# RaspiOmix.net
KiCad netlist of a schematic drawn in EAGLE
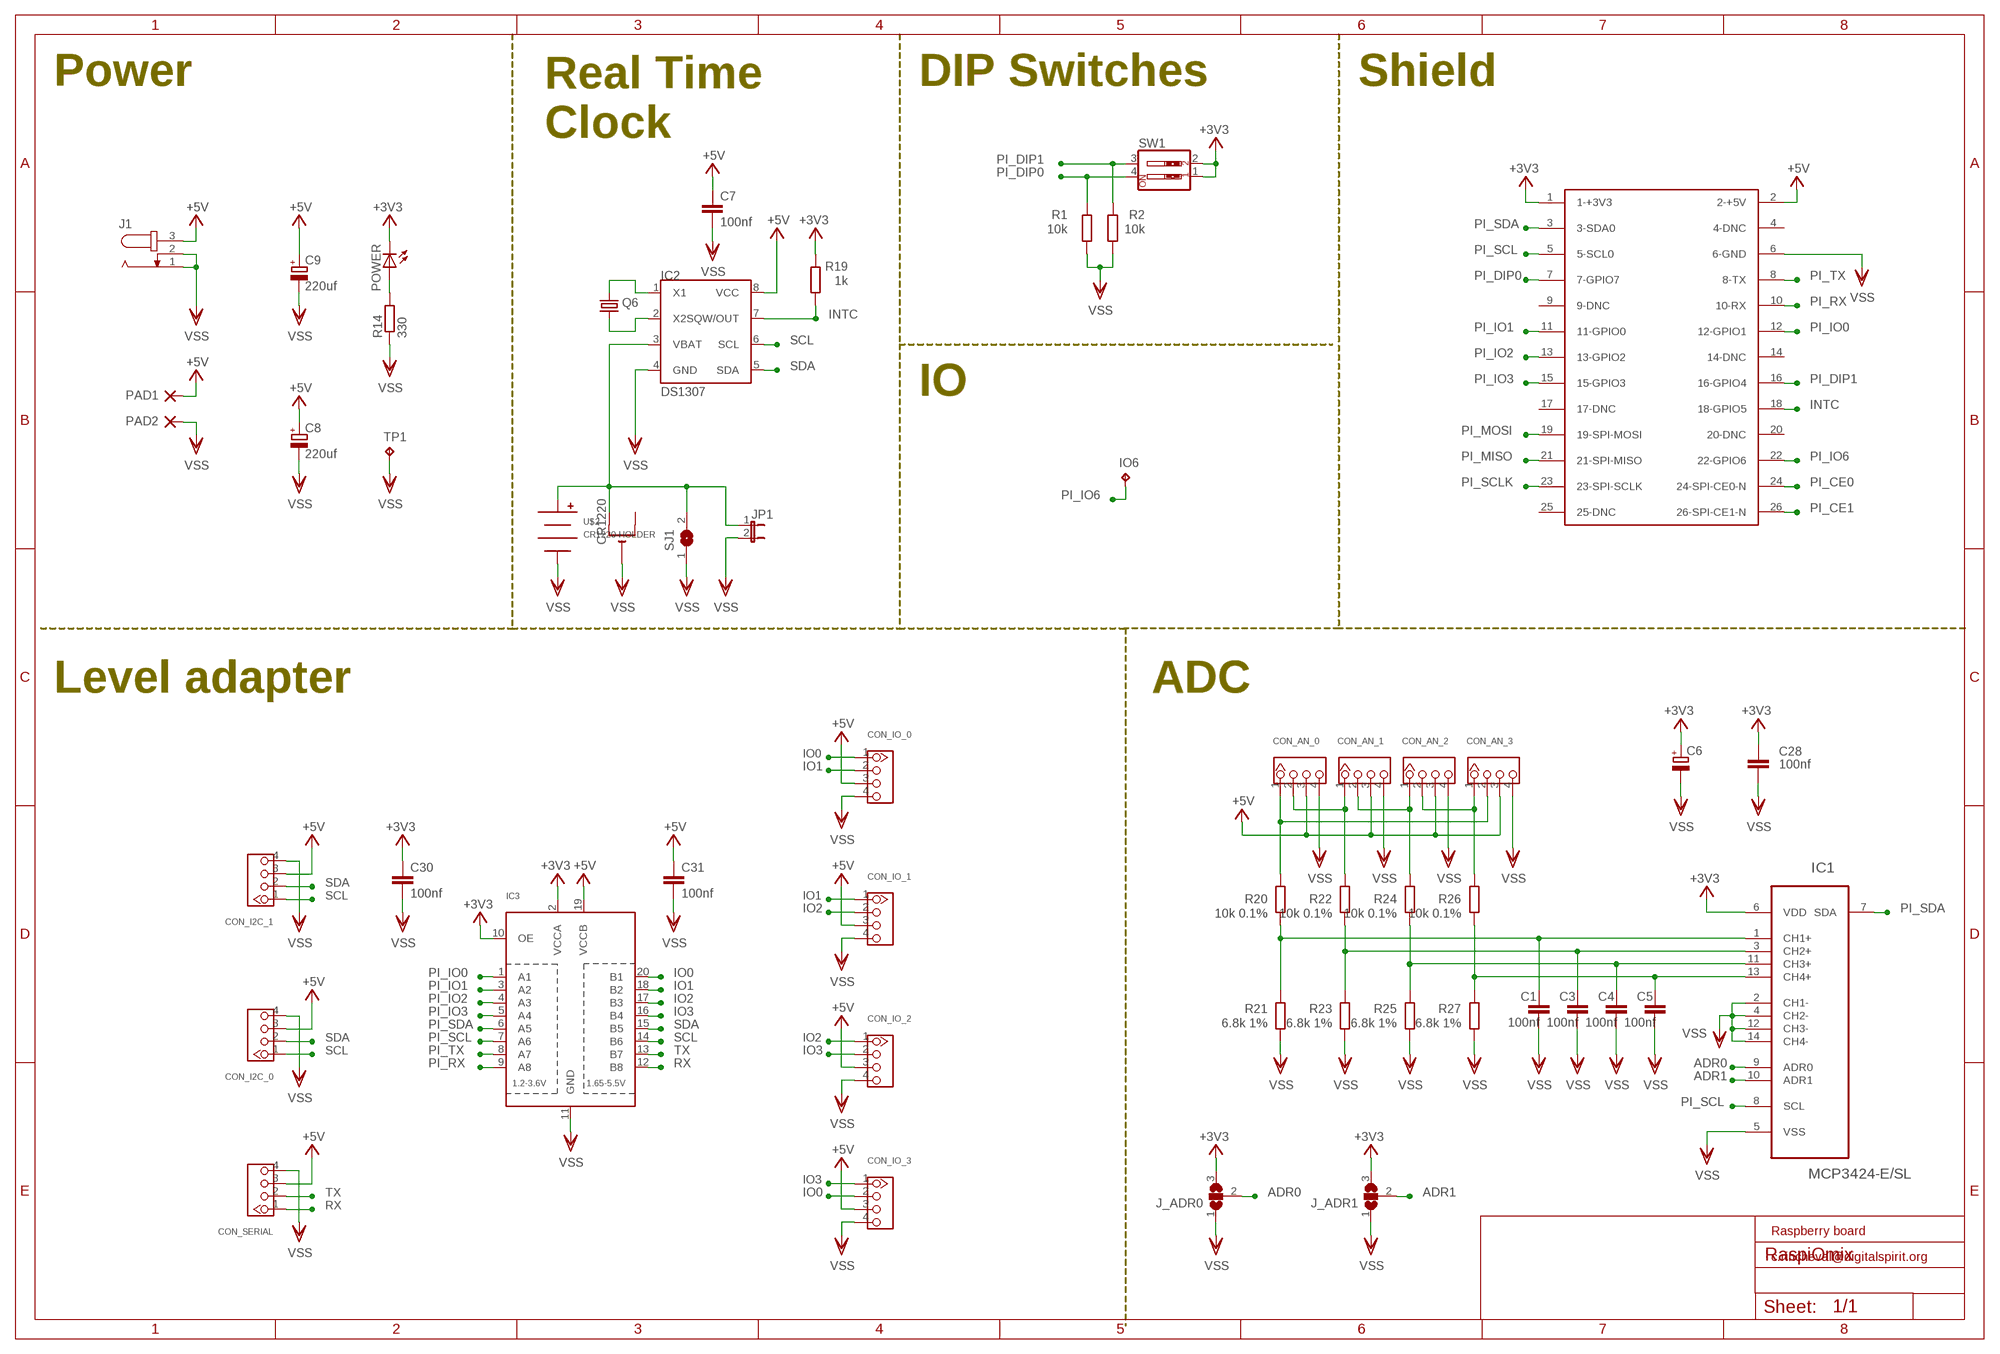
[diagram p0: schematic, sheet 1]

(export (version "E")
  (design (tool "Eeschema 10.0.6"))
  (components
    (comp (ref "C1")
      (value "100nf")
      (footprint "eagle-import:C0805")
      (libsource (lib "eagle-import") (part "C-EUC0805"))
    )
    (comp (ref "C3")
      (value "100nf")
      (footprint "eagle-import:C0805")
      (libsource (lib "eagle-import") (part "C-EUC0805"))
    )
    (comp (ref "C4")
      (value "100nf")
      (footprint "eagle-import:C0805")
      (libsource (lib "eagle-import") (part "C-EUC0805"))
    )
    (comp (ref "C5")
      (value "100nf")
      (footprint "eagle-import:C0805")
      (libsource (lib "eagle-import") (part "C-EUC0805"))
    )
    (comp (ref "C6")
      (value "CPOL-EUB/3528-21R")
      (footprint "eagle-import:B_3528-21R")
      (libsource (lib "eagle-import") (part "CPOL-EUB/3528-21R"))
    )
    (comp (ref "C7")
      (value "100nf")
      (footprint "eagle-import:C0805")
      (libsource (lib "eagle-import") (part "C-EUC0805"))
    )
    (comp (ref "C8")
      (value "220uf")
      (footprint "eagle-import:PANASONIC_D")
      (libsource (lib "eagle-import") (part "CPOL-EUD"))
    )
    (comp (ref "C9")
      (value "220uf")
      (footprint "eagle-import:PANASONIC_D")
      (libsource (lib "eagle-import") (part "CPOL-EUD"))
    )
    (comp (ref "C28")
      (value "100nf")
      (footprint "eagle-import:C0805")
      (libsource (lib "eagle-import") (part "C-EUC0805"))
    )
    (comp (ref "C30")
      (value "100nf")
      (footprint "eagle-import:C0805")
      (libsource (lib "eagle-import") (part "C-EUC0805"))
    )
    (comp (ref "C31")
      (value "100nf")
      (footprint "eagle-import:C0805")
      (libsource (lib "eagle-import") (part "C-EUC0805"))
    )
    (comp (ref "CON_AN_0")
      (value "TWIG-4P-2.0'90D'")
      (footprint "eagle-import:4P-2.0-90D")
      (libsource (lib "eagle-import") (part "TWIG-4P-2.0'90D'"))
    )
    (comp (ref "CON_AN_1")
      (value "TWIG-4P-2.0'90D'")
      (footprint "eagle-import:4P-2.0-90D")
      (libsource (lib "eagle-import") (part "TWIG-4P-2.0'90D'"))
    )
    (comp (ref "CON_AN_2")
      (value "TWIG-4P-2.0'90D'")
      (footprint "eagle-import:4P-2.0-90D")
      (libsource (lib "eagle-import") (part "TWIG-4P-2.0'90D'"))
    )
    (comp (ref "CON_AN_3")
      (value "TWIG-4P-2.0'90D'")
      (footprint "eagle-import:4P-2.0-90D")
      (libsource (lib "eagle-import") (part "TWIG-4P-2.0'90D'"))
    )
    (comp (ref "CON_I2C_0")
      (value "TWIG-4P-2.0'90D'")
      (footprint "eagle-import:4P-2.0-90D")
      (libsource (lib "eagle-import") (part "TWIG-4P-2.0'90D'"))
    )
    (comp (ref "CON_I2C_1")
      (value "TWIG-4P-2.0'90D'")
      (footprint "eagle-import:4P-2.0-90D")
      (libsource (lib "eagle-import") (part "TWIG-4P-2.0'90D'"))
    )
    (comp (ref "CON_IO_0")
      (value "TWIG-4P-2.0'90D'")
      (footprint "eagle-import:4P-2.0-90D")
      (libsource (lib "eagle-import") (part "TWIG-4P-2.0'90D'"))
    )
    (comp (ref "CON_IO_1")
      (value "TWIG-4P-2.0'90D'")
      (footprint "eagle-import:4P-2.0-90D")
      (libsource (lib "eagle-import") (part "TWIG-4P-2.0'90D'"))
    )
    (comp (ref "CON_IO_2")
      (value "TWIG-4P-2.0'90D'")
      (footprint "eagle-import:4P-2.0-90D")
      (libsource (lib "eagle-import") (part "TWIG-4P-2.0'90D'"))
    )
    (comp (ref "CON_IO_3")
      (value "TWIG-4P-2.0'90D'")
      (footprint "eagle-import:4P-2.0-90D")
      (libsource (lib "eagle-import") (part "TWIG-4P-2.0'90D'"))
    )
    (comp (ref "CON_SERIAL")
      (value "TWIG-4P-2.0'90D'")
      (footprint "eagle-import:4P-2.0-90D")
      (libsource (lib "eagle-import") (part "TWIG-4P-2.0'90D'"))
    )
    (comp (ref "CR1220")
      (value "CR1220THM")
      (footprint "eagle-import:CR1220-THM")
      (libsource (lib "eagle-import") (part "CR1220THM"))
    )
    (comp (ref "IC1")
      (value "MCP3424-E/SL")
      (footprint "eagle-import:SOIC-14")
      (libsource (lib "eagle-import") (part "MCP3424-E/SL"))
    )
    (comp (ref "IC2")
      (value "DS1307")
      (footprint "eagle-import:SOIC-8")
      (libsource (lib "eagle-import") (part "DS1307"))
    )
    (comp (ref "IC3")
      (value "TXB0108PWR")
      (footprint "eagle-import:TSSOP20")
      (libsource (lib "eagle-import") (part "TXB0108PWR"))
    )
    (comp (ref "IO6")
      (value "TPPAD1-13")
      (footprint "eagle-import:P1-13")
      (libsource (lib "eagle-import") (part "TPPAD1-13"))
    )
    (comp (ref "J1")
      (value "JACK-PLUG0")
      (footprint "eagle-import:SPC4077")
      (libsource (lib "eagle-import") (part "JACK-PLUG0"))
    )
    (comp (ref "JP1")
      (value "JP1E")
      (footprint "eagle-import:JP1")
      (libsource (lib "eagle-import") (part "JP1E"))
    )
    (comp (ref "J_ADR0")
      (value "SJ2W")
      (footprint "eagle-import:SJ_2")
      (libsource (lib "eagle-import") (part "SJ2W"))
    )
    (comp (ref "J_ADR1")
      (value "SJ2W")
      (footprint "eagle-import:SJ_2")
      (libsource (lib "eagle-import") (part "SJ2W"))
    )
    (comp (ref "PAD1")
      (value "WIREPAD3,17/1,3")
      (footprint "eagle-import:3,17_1,3")
      (libsource (lib "eagle-import") (part "WIREPAD3,17/1,3"))
    )
    (comp (ref "PAD2")
      (value "WIREPAD3,17/1,3")
      (footprint "eagle-import:3,17_1,3")
      (libsource (lib "eagle-import") (part "WIREPAD3,17/1,3"))
    )
    (comp (ref "POWER")
      (value "LEDCHIPLED_0805")
      (footprint "eagle-import:CHIPLED_0805")
      (libsource (lib "eagle-import") (part "LEDCHIPLED_0805"))
    )
    (comp (ref "Q6")
      (value "CRYSTALTC26H")
      (footprint "eagle-import:TC26H")
      (libsource (lib "eagle-import") (part "CRYSTALTC26H"))
    )
    (comp (ref "R1")
      (value "10k")
      (footprint "eagle-import:M0805")
      (libsource (lib "eagle-import") (part "R-EU_M0805"))
    )
    (comp (ref "R2")
      (value "10k")
      (footprint "eagle-import:M0805")
      (libsource (lib "eagle-import") (part "R-EU_M0805"))
    )
    (comp (ref "R14")
      (value "330")
      (footprint "eagle-import:M0805")
      (libsource (lib "eagle-import") (part "R-EU_M0805"))
    )
    (comp (ref "R19")
      (value "1k")
      (footprint "eagle-import:M0805")
      (libsource (lib "eagle-import") (part "R-EU_M0805"))
    )
    (comp (ref "R20")
      (value "10k 0.1%")
      (footprint "eagle-import:M0805")
      (libsource (lib "eagle-import") (part "R-EU_M0805"))
    )
    (comp (ref "R21")
      (value "6.8k 1%")
      (footprint "eagle-import:M0805")
      (libsource (lib "eagle-import") (part "R-EU_M0805"))
    )
    (comp (ref "R22")
      (value "10k 0.1%")
      (footprint "eagle-import:M0805")
      (libsource (lib "eagle-import") (part "R-EU_M0805"))
    )
    (comp (ref "R23")
      (value "6.8k 1%")
      (footprint "eagle-import:M0805")
      (libsource (lib "eagle-import") (part "R-EU_M0805"))
    )
    (comp (ref "R24")
      (value "10k 0.1%")
      (footprint "eagle-import:M0805")
      (libsource (lib "eagle-import") (part "R-EU_M0805"))
    )
    (comp (ref "R25")
      (value "6.8k 1%")
      (footprint "eagle-import:M0805")
      (libsource (lib "eagle-import") (part "R-EU_M0805"))
    )
    (comp (ref "R26")
      (value "10k 0.1%")
      (footprint "eagle-import:M0805")
      (libsource (lib "eagle-import") (part "R-EU_M0805"))
    )
    (comp (ref "R27")
      (value "6.8k 1%")
      (footprint "eagle-import:M0805")
      (libsource (lib "eagle-import") (part "R-EU_M0805"))
    )
    (comp (ref "SJ1") (value "SJ") (footprint "eagle-import:SJ") (libsource (lib "eagle-import") (part "SJ")))
    (comp (ref "SW1")
      (value "SW_DIP-2")
      (footprint "eagle-import:EDG-02")
      (libsource (lib "eagle-import") (part "SW_DIP-2"))
    )
    (comp (ref "TP1")
      (value "TPPAD1-13")
      (footprint "eagle-import:P1-13")
      (libsource (lib "eagle-import") (part "TPPAD1-13"))
    )
    (comp (ref "U$2")
      (value "CR1220-HOLDER")
      (footprint "eagle-import:HARWIN-CR1220")
      (libsource (lib "eagle-import") (part "CR1220-HOLDER"))
    )
    (comp (ref "U$3")
      (value "RASPBERRY-PILIGHT-HOLE")
      (footprint "eagle-import:RASPBERRY-PI-LIGHT-HOLE")
      (libsource (lib "eagle-import") (part "RASPBERRY-PILIGHT-HOLE"))
    )
  )
  (nets
    (net (code "1") (name "+3V3") (class "Default")
      (node (ref "C28") (pin "2") (pinfunction "2_2") (pintype "passive"))
      (node (ref "C30") (pin "1") (pinfunction "1_1") (pintype "passive"))
      (node (ref "C6") (pin "+") (pinfunction "+_+") (pintype "passive"))
      (node (ref "IC1") (pin "6") (pinfunction "VDD_6") (pintype "power_in"))
      (node (ref "IC3") (pin "10") (pinfunction "OE_10") (pintype "bidirectional"))
      (node (ref "IC3") (pin "2") (pinfunction "VCCA_2") (pintype "bidirectional"))
      (node (ref "J_ADR0") (pin "3") (pinfunction "3_3") (pintype "passive"))
      (node (ref "J_ADR1") (pin "3") (pinfunction "3_3") (pintype "passive"))
      (node (ref "POWER") (pin "C") (pinfunction "C_C") (pintype "passive"))
      (node (ref "R19") (pin "2") (pinfunction "2_2") (pintype "passive"))
      (node (ref "SW1") (pin "1") (pinfunction "1_1") (pintype "passive"))
      (node (ref "SW1") (pin "2") (pinfunction "2_2") (pintype "passive"))
      (node (ref "U$3") (pin "1") (pinfunction "1-+3V3_1") (pintype "bidirectional"))
    )
    (net (code "2") (name "+5V") (class "Default")
      (node (ref "C31") (pin "1") (pinfunction "1_1") (pintype "passive"))
      (node (ref "C7") (pin "1") (pinfunction "1_1") (pintype "passive"))
      (node (ref "C8") (pin "+") (pinfunction "+_+") (pintype "passive"))
      (node (ref "C9") (pin "+") (pinfunction "+_+") (pintype "passive"))
      (node (ref "CON_AN_0") (pin "3") (pinfunction "3_3") (pintype "bidirectional"))
      (node (ref "CON_AN_1") (pin "3") (pinfunction "3_3") (pintype "bidirectional"))
      (node (ref "CON_AN_2") (pin "3") (pinfunction "3_3") (pintype "bidirectional"))
      (node (ref "CON_AN_3") (pin "3") (pinfunction "3_3") (pintype "bidirectional"))
      (node (ref "CON_I2C_0") (pin "3") (pinfunction "3_3") (pintype "bidirectional"))
      (node (ref "CON_I2C_1") (pin "3") (pinfunction "3_3") (pintype "bidirectional"))
      (node (ref "CON_IO_0") (pin "3") (pinfunction "3_3") (pintype "bidirectional"))
      (node (ref "CON_IO_1") (pin "3") (pinfunction "3_3") (pintype "bidirectional"))
      (node (ref "CON_IO_2") (pin "3") (pinfunction "3_3") (pintype "bidirectional"))
      (node (ref "CON_IO_3") (pin "3") (pinfunction "3_3") (pintype "bidirectional"))
      (node (ref "CON_SERIAL") (pin "3") (pinfunction "3_3") (pintype "bidirectional"))
      (node (ref "IC2") (pin "8") (pinfunction "VCC_8") (pintype "power_in"))
      (node (ref "IC3") (pin "19") (pinfunction "VCCB_19") (pintype "bidirectional"))
      (node (ref "J1") (pin "3") (pinfunction "3_3") (pintype "passive"))
      (node (ref "PAD1") (pin "1") (pinfunction "P_1") (pintype "passive"))
      (node (ref "U$3") (pin "2") (pinfunction "2-+5V_2") (pintype "bidirectional"))
    )
    (net (code "3") (name "/ADR0") (class "Default")
      (node (ref "IC1") (pin "9") (pinfunction "ADR0_9") (pintype "input"))
      (node (ref "J_ADR0") (pin "2") (pinfunction "2_2") (pintype "passive"))
    )
    (net (code "4") (name "/ADR1") (class "Default")
      (node (ref "IC1") (pin "10") (pinfunction "ADR1_10") (pintype "input"))
      (node (ref "J_ADR1") (pin "2") (pinfunction "2_2") (pintype "passive"))
    )
    (net (code "5") (name "/INTC") (class "Default")
      (node (ref "IC2") (pin "7") (pinfunction "SQW/OUT_7") (pintype "output"))
      (node (ref "R19") (pin "1") (pinfunction "1_1") (pintype "passive"))
      (node (ref "U$3") (pin "18") (pinfunction "18-GPIO5_18") (pintype "bidirectional"))
    )
    (net (code "6") (name "/IO0") (class "Default")
      (node (ref "CON_IO_0") (pin "1") (pinfunction "1_1") (pintype "bidirectional"))
      (node (ref "CON_IO_3") (pin "2") (pinfunction "2_2") (pintype "bidirectional"))
      (node (ref "IC3") (pin "20") (pinfunction "B1_20") (pintype "bidirectional"))
    )
    (net (code "7") (name "/IO1") (class "Default")
      (node (ref "CON_IO_0") (pin "2") (pinfunction "2_2") (pintype "bidirectional"))
      (node (ref "CON_IO_1") (pin "1") (pinfunction "1_1") (pintype "bidirectional"))
      (node (ref "IC3") (pin "18") (pinfunction "B2_18") (pintype "bidirectional"))
    )
    (net (code "8") (name "/IO2") (class "Default")
      (node (ref "CON_IO_1") (pin "2") (pinfunction "2_2") (pintype "bidirectional"))
      (node (ref "CON_IO_2") (pin "1") (pinfunction "1_1") (pintype "bidirectional"))
      (node (ref "IC3") (pin "17") (pinfunction "B3_17") (pintype "bidirectional"))
    )
    (net (code "9") (name "/IO3") (class "Default")
      (node (ref "CON_IO_2") (pin "2") (pinfunction "2_2") (pintype "bidirectional"))
      (node (ref "CON_IO_3") (pin "1") (pinfunction "1_1") (pintype "bidirectional"))
      (node (ref "IC3") (pin "16") (pinfunction "B4_16") (pintype "bidirectional"))
    )
    (net (code "10") (name "/PI_CE0") (class "Default")
      (node (ref "U$3") (pin "24") (pinfunction "24-SPI-CE0-N_24") (pintype "bidirectional"))
    )
    (net (code "11") (name "/PI_CE1") (class "Default")
      (node (ref "U$3") (pin "26") (pinfunction "26-SPI-CE1-N_26") (pintype "bidirectional"))
    )
    (net (code "12") (name "/PI_DIP0") (class "Default")
      (node (ref "R1") (pin "2") (pinfunction "2_2") (pintype "passive"))
      (node (ref "SW1") (pin "4") (pinfunction "4_4") (pintype "passive"))
      (node (ref "U$3") (pin "7") (pinfunction "7-GPIO7_7") (pintype "bidirectional"))
    )
    (net (code "13") (name "/PI_DIP1") (class "Default")
      (node (ref "R2") (pin "2") (pinfunction "2_2") (pintype "passive"))
      (node (ref "SW1") (pin "3") (pinfunction "3_3") (pintype "passive"))
      (node (ref "U$3") (pin "16") (pinfunction "16-GPIO4_16") (pintype "bidirectional"))
    )
    (net (code "14") (name "/PI_IO0") (class "Default")
      (node (ref "IC3") (pin "1") (pinfunction "A1_1") (pintype "bidirectional"))
      (node (ref "U$3") (pin "12") (pinfunction "12-GPIO1_12") (pintype "bidirectional"))
    )
    (net (code "15") (name "/PI_IO1") (class "Default")
      (node (ref "IC3") (pin "3") (pinfunction "A2_3") (pintype "bidirectional"))
      (node (ref "U$3") (pin "11") (pinfunction "11-GPIO0_11") (pintype "bidirectional"))
    )
    (net (code "16") (name "/PI_IO2") (class "Default")
      (node (ref "IC3") (pin "4") (pinfunction "A3_4") (pintype "bidirectional"))
      (node (ref "U$3") (pin "13") (pinfunction "13-GPIO2_13") (pintype "bidirectional"))
    )
    (net (code "17") (name "/PI_IO3") (class "Default")
      (node (ref "IC3") (pin "5") (pinfunction "A4_5") (pintype "bidirectional"))
      (node (ref "U$3") (pin "15") (pinfunction "15-GPIO3_15") (pintype "bidirectional"))
    )
    (net (code "18") (name "/PI_IO6") (class "Default")
      (node (ref "IO6") (pin "TP") (pinfunction "TP_TP") (pintype "input"))
      (node (ref "U$3") (pin "22") (pinfunction "22-GPIO6_22") (pintype "bidirectional"))
    )
    (net (code "19") (name "/PI_MISO") (class "Default")
      (node (ref "U$3") (pin "21") (pinfunction "21-SPI-MISO_21") (pintype "bidirectional"))
    )
    (net (code "20") (name "/PI_MOSI") (class "Default")
      (node (ref "U$3") (pin "19") (pinfunction "19-SPI-MOSI_19") (pintype "bidirectional"))
    )
    (net (code "21") (name "/PI_RX") (class "Default")
      (node (ref "IC3") (pin "9") (pinfunction "A8_9") (pintype "bidirectional"))
      (node (ref "U$3") (pin "10") (pinfunction "10-RX_10") (pintype "bidirectional"))
    )
    (net (code "22") (name "/PI_SCL") (class "Default")
      (node (ref "IC1") (pin "8") (pinfunction "SCL_8") (pintype "input"))
      (node (ref "IC3") (pin "7") (pinfunction "A6_7") (pintype "bidirectional"))
      (node (ref "U$3") (pin "5") (pinfunction "5-SCL0_5") (pintype "bidirectional"))
    )
    (net (code "23") (name "/PI_SCLK") (class "Default")
      (node (ref "U$3") (pin "23") (pinfunction "23-SPI-SCLK_23") (pintype "bidirectional"))
    )
    (net (code "24") (name "/PI_SDA") (class "Default")
      (node (ref "IC1") (pin "7") (pinfunction "SDA_7") (pintype "bidirectional"))
      (node (ref "IC3") (pin "6") (pinfunction "A5_6") (pintype "bidirectional"))
      (node (ref "U$3") (pin "3") (pinfunction "3-SDA0_3") (pintype "bidirectional"))
    )
    (net (code "25") (name "/PI_TX") (class "Default")
      (node (ref "IC3") (pin "8") (pinfunction "A7_8") (pintype "bidirectional"))
      (node (ref "U$3") (pin "8") (pinfunction "8-TX_8") (pintype "bidirectional"))
    )
    (net (code "26") (name "/RX") (class "Default")
      (node (ref "CON_SERIAL") (pin "1") (pinfunction "1_1") (pintype "bidirectional"))
      (node (ref "IC3") (pin "12") (pinfunction "B8_12") (pintype "bidirectional"))
    )
    (net (code "27") (name "/SCL") (class "Default")
      (node (ref "CON_I2C_0") (pin "1") (pinfunction "1_1") (pintype "bidirectional"))
      (node (ref "CON_I2C_1") (pin "1") (pinfunction "1_1") (pintype "bidirectional"))
      (node (ref "IC2") (pin "6") (pinfunction "SCL_6") (pintype "input"))
      (node (ref "IC3") (pin "14") (pinfunction "B6_14") (pintype "bidirectional"))
    )
    (net (code "28") (name "/SDA") (class "Default")
      (node (ref "CON_I2C_0") (pin "2") (pinfunction "2_2") (pintype "bidirectional"))
      (node (ref "CON_I2C_1") (pin "2") (pinfunction "2_2") (pintype "bidirectional"))
      (node (ref "IC2") (pin "5") (pinfunction "SDA_5") (pintype "bidirectional"))
      (node (ref "IC3") (pin "15") (pinfunction "B5_15") (pintype "bidirectional"))
    )
    (net (code "29") (name "/TX") (class "Default")
      (node (ref "CON_SERIAL") (pin "2") (pinfunction "2_2") (pintype "bidirectional"))
      (node (ref "IC3") (pin "13") (pinfunction "B7_13") (pintype "bidirectional"))
    )
    (net (code "30") (name "Net-(CON_AN_0-Pad1)") (class "Default")
      (node (ref "CON_AN_0") (pin "1") (pinfunction "1_1") (pintype "bidirectional"))
      (node (ref "CON_AN_3") (pin "2") (pinfunction "2_2") (pintype "bidirectional"))
      (node (ref "R20") (pin "2") (pinfunction "2_2") (pintype "passive"))
    )
    (net (code "31") (name "Net-(CON_AN_0-Pad2)") (class "Default")
      (node (ref "CON_AN_0") (pin "2") (pinfunction "2_2") (pintype "bidirectional"))
      (node (ref "CON_AN_1") (pin "1") (pinfunction "1_1") (pintype "bidirectional"))
      (node (ref "R22") (pin "2") (pinfunction "2_2") (pintype "passive"))
    )
    (net (code "32") (name "Net-(CON_AN_1-Pad2)") (class "Default")
      (node (ref "CON_AN_1") (pin "2") (pinfunction "2_2") (pintype "bidirectional"))
      (node (ref "CON_AN_2") (pin "1") (pinfunction "1_1") (pintype "bidirectional"))
      (node (ref "R24") (pin "2") (pinfunction "2_2") (pintype "passive"))
    )
    (net (code "33") (name "Net-(CON_AN_2-Pad2)") (class "Default")
      (node (ref "CON_AN_2") (pin "2") (pinfunction "2_2") (pintype "bidirectional"))
      (node (ref "CON_AN_3") (pin "1") (pinfunction "1_1") (pintype "bidirectional"))
      (node (ref "R26") (pin "2") (pinfunction "2_2") (pintype "passive"))
    )
    (net (code "34") (name "Net-(CR1220-+)") (class "Default")
      (node (ref "CR1220") (pin "+1") (pinfunction "+_+1") (pintype "passive"))
      (node (ref "IC2") (pin "3") (pinfunction "VBAT_3") (pintype "power_in"))
      (node (ref "JP1") (pin "1") (pinfunction "1_1") (pintype "passive"))
      (node (ref "SJ1") (pin "2") (pinfunction "2_2") (pintype "passive"))
      (node (ref "U$2") (pin "POS") (pinfunction "POS_POS") (pintype "bidirectional"))
    )
    (net (code "35") (name "Net-(IC1-CH1+)") (class "Default")
      (node (ref "C1") (pin "1") (pinfunction "1_1") (pintype "passive"))
      (node (ref "IC1") (pin "1") (pinfunction "CH1+_1") (pintype "input"))
      (node (ref "R20") (pin "1") (pinfunction "1_1") (pintype "passive"))
      (node (ref "R21") (pin "2") (pinfunction "2_2") (pintype "passive"))
    )
    (net (code "36") (name "Net-(IC1-CH2+)") (class "Default")
      (node (ref "C3") (pin "1") (pinfunction "1_1") (pintype "passive"))
      (node (ref "IC1") (pin "3") (pinfunction "CH2+_3") (pintype "input"))
      (node (ref "R22") (pin "1") (pinfunction "1_1") (pintype "passive"))
      (node (ref "R23") (pin "2") (pinfunction "2_2") (pintype "passive"))
    )
    (net (code "37") (name "Net-(IC1-CH3+)") (class "Default")
      (node (ref "C4") (pin "1") (pinfunction "1_1") (pintype "passive"))
      (node (ref "IC1") (pin "11") (pinfunction "CH3+_11") (pintype "input"))
      (node (ref "R24") (pin "1") (pinfunction "1_1") (pintype "passive"))
      (node (ref "R25") (pin "2") (pinfunction "2_2") (pintype "passive"))
    )
    (net (code "38") (name "Net-(IC1-CH4+)") (class "Default")
      (node (ref "C5") (pin "1") (pinfunction "1_1") (pintype "passive"))
      (node (ref "IC1") (pin "13") (pinfunction "CH4+_13") (pintype "input"))
      (node (ref "R26") (pin "1") (pinfunction "1_1") (pintype "passive"))
      (node (ref "R27") (pin "2") (pinfunction "2_2") (pintype "passive"))
    )
    (net (code "39") (name "Net-(IC2-X1)") (class "Default")
      (node (ref "IC2") (pin "1") (pinfunction "X1_1") (pintype "input"))
      (node (ref "Q6") (pin "1") (pinfunction "1_1") (pintype "passive"))
    )
    (net (code "40") (name "Net-(IC2-X2)") (class "Default")
      (node (ref "IC2") (pin "2") (pinfunction "X2_2") (pintype "output"))
      (node (ref "Q6") (pin "2") (pinfunction "2_2") (pintype "passive"))
    )
    (net (code "41") (name "Net-(POWER-PadA)") (class "Default")
      (node (ref "POWER") (pin "A") (pinfunction "A_A") (pintype "passive"))
      (node (ref "R14") (pin "2") (pinfunction "2_2") (pintype "passive"))
    )
    (net (code "42") (name "VSS") (class "Default")
      (node (ref "C1") (pin "2") (pinfunction "2_2") (pintype "passive"))
      (node (ref "C28") (pin "1") (pinfunction "1_1") (pintype "passive"))
      (node (ref "C3") (pin "2") (pinfunction "2_2") (pintype "passive"))
      (node (ref "C30") (pin "2") (pinfunction "2_2") (pintype "passive"))
      (node (ref "C31") (pin "2") (pinfunction "2_2") (pintype "passive"))
      (node (ref "C4") (pin "2") (pinfunction "2_2") (pintype "passive"))
      (node (ref "C5") (pin "2") (pinfunction "2_2") (pintype "passive"))
      (node (ref "C6") (pin "-") (pinfunction "-_-") (pintype "passive"))
      (node (ref "C7") (pin "2") (pinfunction "2_2") (pintype "passive"))
      (node (ref "C8") (pin "-") (pinfunction "-_-") (pintype "passive"))
      (node (ref "C9") (pin "-") (pinfunction "-_-") (pintype "passive"))
      (node (ref "CON_AN_0") (pin "4") (pinfunction "4_4") (pintype "bidirectional"))
      (node (ref "CON_AN_1") (pin "4") (pinfunction "4_4") (pintype "bidirectional"))
      (node (ref "CON_AN_2") (pin "4") (pinfunction "4_4") (pintype "bidirectional"))
      (node (ref "CON_AN_3") (pin "4") (pinfunction "4_4") (pintype "bidirectional"))
      (node (ref "CON_I2C_0") (pin "4") (pinfunction "4_4") (pintype "bidirectional"))
      (node (ref "CON_I2C_1") (pin "4") (pinfunction "4_4") (pintype "bidirectional"))
      (node (ref "CON_IO_0") (pin "4") (pinfunction "4_4") (pintype "bidirectional"))
      (node (ref "CON_IO_1") (pin "4") (pinfunction "4_4") (pintype "bidirectional"))
      (node (ref "CON_IO_2") (pin "4") (pinfunction "4_4") (pintype "bidirectional"))
      (node (ref "CON_IO_3") (pin "4") (pinfunction "4_4") (pintype "bidirectional"))
      (node (ref "CON_SERIAL") (pin "4") (pinfunction "4_4") (pintype "bidirectional"))
      (node (ref "CR1220") (pin "-") (pinfunction "-_-") (pintype "passive"))
      (node (ref "IC1") (pin "12") (pinfunction "CH3-_12") (pintype "input"))
      (node (ref "IC1") (pin "14") (pinfunction "CH4-_14") (pintype "input"))
      (node (ref "IC1") (pin "2") (pinfunction "CH1-_2") (pintype "input"))
      (node (ref "IC1") (pin "4") (pinfunction "CH2-_4") (pintype "input"))
      (node (ref "IC1") (pin "5") (pinfunction "VSS_5") (pintype "power_in"))
      (node (ref "IC2") (pin "4") (pinfunction "GND_4") (pintype "power_in"))
      (node (ref "IC3") (pin "11") (pinfunction "GND_11") (pintype "bidirectional"))
      (node (ref "J1") (pin "1") (pinfunction "1_1") (pintype "passive"))
      (node (ref "J1") (pin "2") (pinfunction "2_2") (pintype "passive"))
      (node (ref "JP1") (pin "2") (pinfunction "2_2") (pintype "passive"))
      (node (ref "J_ADR0") (pin "1") (pinfunction "1_1") (pintype "passive"))
      (node (ref "J_ADR1") (pin "1") (pinfunction "1_1") (pintype "passive"))
      (node (ref "PAD2") (pin "1") (pinfunction "P_1") (pintype "passive"))
      (node (ref "R1") (pin "1") (pinfunction "1_1") (pintype "passive"))
      (node (ref "R14") (pin "1") (pinfunction "1_1") (pintype "passive"))
      (node (ref "R2") (pin "1") (pinfunction "1_1") (pintype "passive"))
      (node (ref "R21") (pin "1") (pinfunction "1_1") (pintype "passive"))
      (node (ref "R23") (pin "1") (pinfunction "1_1") (pintype "passive"))
      (node (ref "R25") (pin "1") (pinfunction "1_1") (pintype "passive"))
      (node (ref "R27") (pin "1") (pinfunction "1_1") (pintype "passive"))
      (node (ref "SJ1") (pin "1") (pinfunction "1_1") (pintype "passive"))
      (node (ref "TP1") (pin "TP") (pinfunction "TP_TP") (pintype "input"))
      (node (ref "U$2") (pin "NEG") (pinfunction "NEG_NEG") (pintype "bidirectional"))
      (node (ref "U$3") (pin "6") (pinfunction "6-GND_6") (pintype "bidirectional"))
    )
    (net (code "43") (name "unconnected-(CR1220-+1-Pad+2)") (class "Default")
      (node (ref "CR1220") (pin "+2") (pinfunction "+1_+2") (pintype "passive"))
    )
    (net (code "44") (name "unconnected-(U$3-4-DNC-Pad4)") (class "Default")
      (node (ref "U$3") (pin "4") (pinfunction "4-DNC_4") (pintype "bidirectional"))
    )
    (net (code "45") (name "unconnected-(U$3-9-DNC-Pad9)") (class "Default")
      (node (ref "U$3") (pin "9") (pinfunction "9-DNC_9") (pintype "bidirectional"))
    )
    (net (code "46") (name "unconnected-(U$3-14-DNC-Pad14)") (class "Default")
      (node (ref "U$3") (pin "14") (pinfunction "14-DNC_14") (pintype "bidirectional"))
    )
    (net (code "47") (name "unconnected-(U$3-17-DNC-Pad17)") (class "Default")
      (node (ref "U$3") (pin "17") (pinfunction "17-DNC_17") (pintype "bidirectional"))
    )
    (net (code "48") (name "unconnected-(U$3-20-DNC-Pad20)") (class "Default")
      (node (ref "U$3") (pin "20") (pinfunction "20-DNC_20") (pintype "bidirectional"))
    )
    (net (code "49") (name "unconnected-(U$3-25-DNC-Pad25)") (class "Default")
      (node (ref "U$3") (pin "25") (pinfunction "25-DNC_25") (pintype "bidirectional"))
    )
  )
)
